# schematic.net
KiCad netlist of a schematic drawn in EAGLE
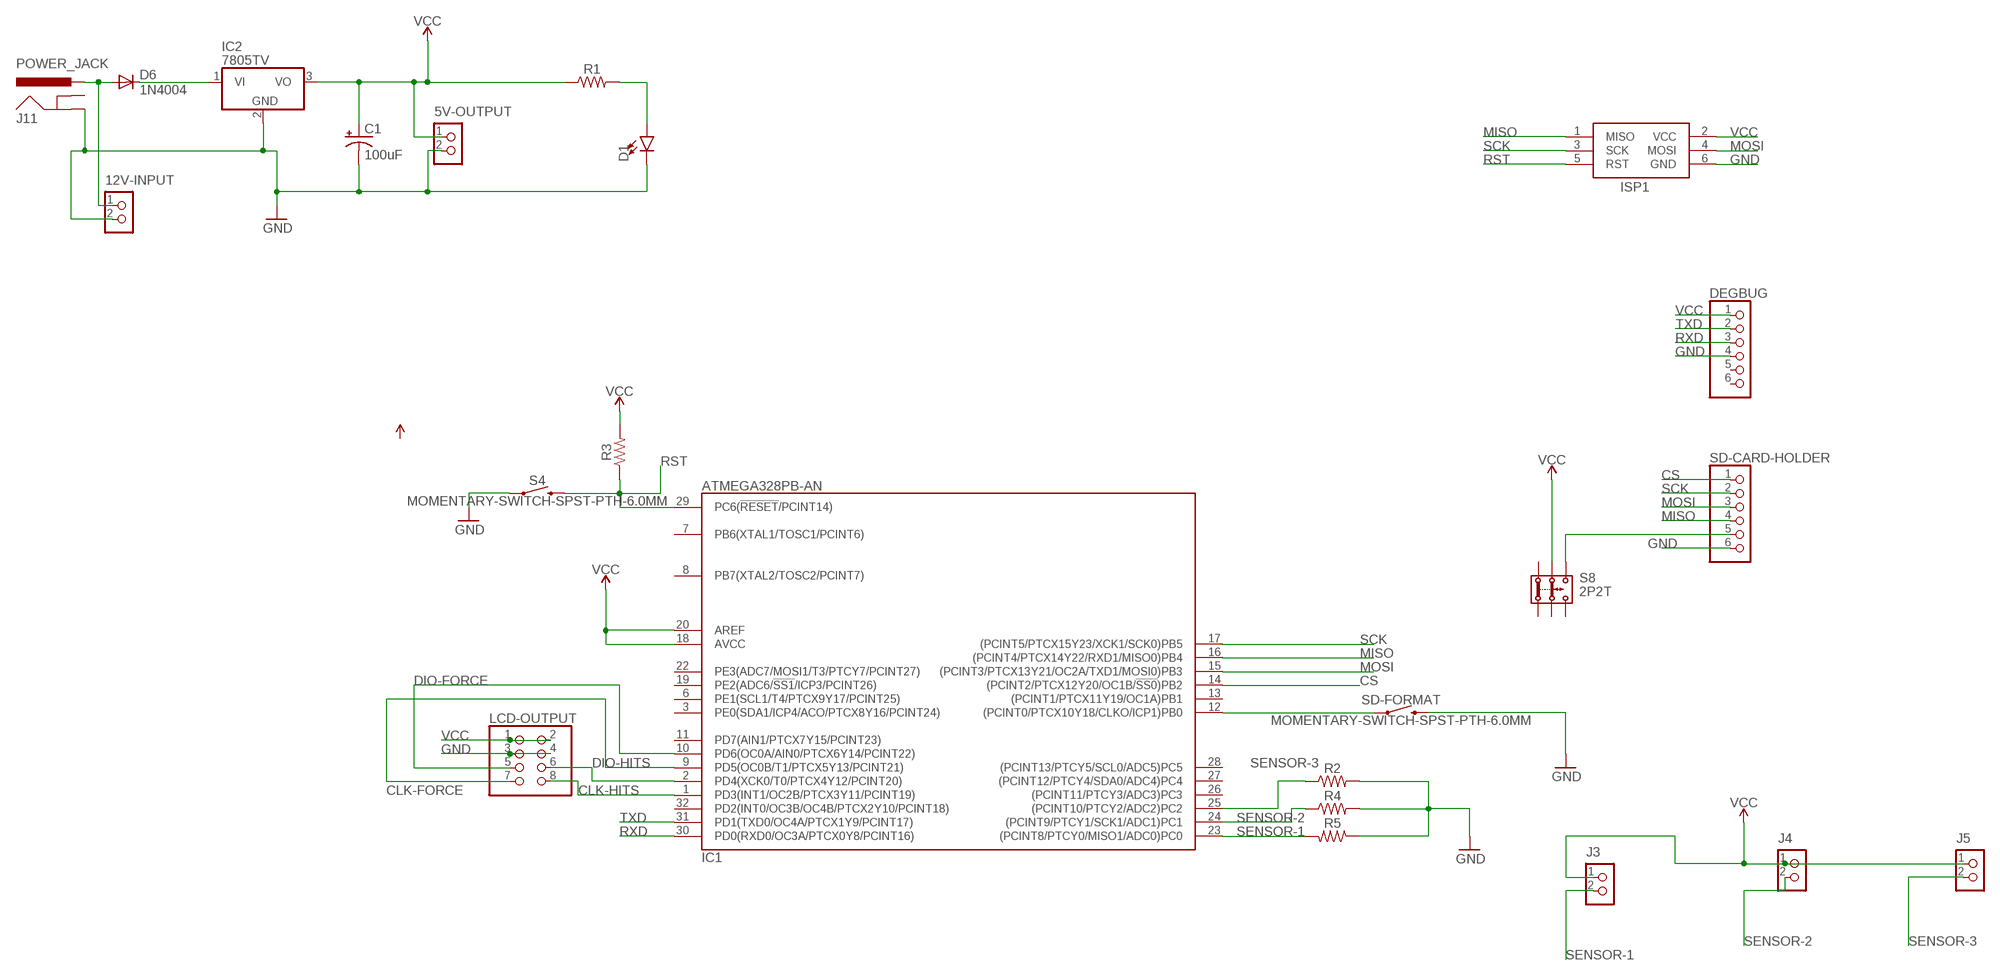
[diagram p0: schematic, sheet 1]

(export (version "E")
  (design (tool "Eeschema 10.0.6"))
  (components
    (comp (ref "5V-OUTPUT")
      (value "CON_TERMINAL_BLOCK_02-5MM")
      (footprint "eagle-import:TERMINAL_BLOCK_2P_5")
      (libsource (lib "eagle-import") (part "CON_TERMINAL_BLOCK_02-5MM"))
    )
    (comp (ref "12V-INPUT")
      (value "CON_TERMINAL_BLOCK_02-5MM")
      (footprint "eagle-import:TERMINAL_BLOCK_2P_5")
      (libsource (lib "eagle-import") (part "CON_TERMINAL_BLOCK_02-5MM"))
    )
    (comp (ref "C1")
      (value "100uF")
      (footprint "eagle-import:CPOL-RADIAL-2.5MM-6.5MM")
      (libsource (lib "eagle-import") (part "100UF-POLAR-RADIAL-2.5MM-25V-20%"))
    )
    (comp (ref "D1")
      (value "LED1206")
      (footprint "eagle-import:LED-1206")
      (libsource (lib "eagle-import") (part "LED1206"))
    )
    (comp (ref "D6")
      (value "1N4004")
      (footprint "eagle-import:DO41-10")
      (libsource (lib "eagle-import") (part "1N4004"))
    )
    (comp (ref "DEGBUG")
      (value "PINHD-1X6")
      (footprint "eagle-import:1X06")
      (libsource (lib "eagle-import") (part "PINHD-1X6"))
    )
    (comp (ref "IC1")
      (value "ATMEGA328PB-AN")
      (footprint "eagle-import:QFP32_7X7_0.80")
      (libsource (lib "eagle-import") (part "ATMEGA328PB-AN"))
    )
    (comp (ref "IC2")
      (value "7805TV")
      (footprint "eagle-import:TO220V")
      (libsource (lib "eagle-import") (part "78TV05"))
    )
    (comp (ref "ISP1")
      (value "AVRISP-6")
      (footprint "eagle-import:AVRISP")
      (libsource (lib "eagle-import") (part "AVRISP-6"))
    )
    (comp (ref "J3")
      (value "CON_TERMINAL_BLOCK_02-5MM")
      (footprint "eagle-import:TERMINAL_BLOCK_2P_5")
      (libsource (lib "eagle-import") (part "CON_TERMINAL_BLOCK_02-5MM"))
    )
    (comp (ref "J4")
      (value "CON_TERMINAL_BLOCK_02-5MM")
      (footprint "eagle-import:TERMINAL_BLOCK_2P_5")
      (libsource (lib "eagle-import") (part "CON_TERMINAL_BLOCK_02-5MM"))
    )
    (comp (ref "J5")
      (value "CON_TERMINAL_BLOCK_02-5MM")
      (footprint "eagle-import:TERMINAL_BLOCK_2P_5")
      (libsource (lib "eagle-import") (part "CON_TERMINAL_BLOCK_02-5MM"))
    )
    (comp (ref "J11")
      (value "POWER_JACK")
      (footprint "eagle-import:POWER_JACK_PTH")
      (libsource (lib "eagle-import") (part "POWER_JACK"))
    )
    (comp (ref "LCD-OUTPUT")
      (value "PINHD-2X4")
      (footprint "eagle-import:2X04")
      (libsource (lib "eagle-import") (part "PINHD-2X4"))
    )
    (comp (ref "R1")
      (value "RESISTOR1206")
      (footprint "eagle-import:1206")
      (libsource (lib "eagle-import") (part "RESISTOR1206"))
    )
    (comp (ref "R2")
      (value "RESISTOR1206")
      (footprint "eagle-import:1206")
      (libsource (lib "eagle-import") (part "RESISTOR1206"))
    )
    (comp (ref "R3")
      (value "RESISTOR1206")
      (footprint "eagle-import:1206")
      (libsource (lib "eagle-import") (part "RESISTOR1206"))
    )
    (comp (ref "R4")
      (value "RESISTOR1206")
      (footprint "eagle-import:1206")
      (libsource (lib "eagle-import") (part "RESISTOR1206"))
    )
    (comp (ref "R5")
      (value "RESISTOR1206")
      (footprint "eagle-import:1206")
      (libsource (lib "eagle-import") (part "RESISTOR1206"))
    )
    (comp (ref "S4")
      (value "MOMENTARY-SWITCH-SPST-PTH-6.0MM")
      (footprint "eagle-import:TACTILE_SWITCH_PTH_6.0MM")
      (libsource (lib "eagle-import") (part "MOMENTARY-SWITCH-SPST-PTH-6.0MM"))
    )
    (comp (ref "S8")
      (value "2P2T")
      (footprint "eagle-import:2P2T")
      (libsource (lib "eagle-import") (part "2P2T"))
    )
    (comp (ref "SD-CARD-HOLDER")
      (value "PINHD-1X6")
      (footprint "eagle-import:1X06")
      (libsource (lib "eagle-import") (part "PINHD-1X6"))
    )
    (comp (ref "SD-FORMAT")
      (value "MOMENTARY-SWITCH-SPST-PTH-6.0MM")
      (footprint "eagle-import:TACTILE_SWITCH_PTH_6.0MM")
      (libsource (lib "eagle-import") (part "MOMENTARY-SWITCH-SPST-PTH-6.0MM"))
    )
  )
  (nets
    (net (code "1") (name "/CLK-FORCE") (class "Default")
      (node (ref "IC1") (pin "9") (pinfunction "PD5(OC0B/T1/PTCX5Y13/PCINT21)_9") (pintype "bidirectional"))
      (node (ref "LCD-OUTPUT") (pin "7") (pinfunction "7_7") (pintype "passive"))
    )
    (net (code "2") (name "/CLK-HITS") (class "Default")
      (node (ref "IC1") (pin "1") (pinfunction "PD3(INT1/OC2B/PTCX3Y11/PCINT19)_1") (pintype "bidirectional"))
      (node (ref "LCD-OUTPUT") (pin "8") (pinfunction "8_8") (pintype "passive"))
    )
    (net (code "3") (name "/CS") (class "Default")
      (node (ref "IC1") (pin "14") (pinfunction "(PCINT2/PTCX12Y20/OC1B/~{SS0})PB2_14") (pintype "bidirectional"))
      (node (ref "SD-CARD-HOLDER") (pin "1") (pinfunction "1_1") (pintype "passive"))
    )
    (net (code "4") (name "/DIO-FORCE") (class "Default")
      (node (ref "IC1") (pin "10") (pinfunction "PD6(OC0A/AIN0/PTCX6Y14/PCINT22)_10") (pintype "bidirectional"))
      (node (ref "LCD-OUTPUT") (pin "5") (pinfunction "5_5") (pintype "passive"))
    )
    (net (code "5") (name "/DIO-HITS") (class "Default")
      (node (ref "IC1") (pin "2") (pinfunction "PD4(XCK0/T0/PTCX4Y12/PCINT20)_2") (pintype "bidirectional"))
      (node (ref "LCD-OUTPUT") (pin "6") (pinfunction "6_6") (pintype "passive"))
    )
    (net (code "6") (name "/MISO") (class "Default")
      (node (ref "IC1") (pin "16") (pinfunction "(PCINT4/PTCX14Y22/RXD1/MISO0)PB4_16") (pintype "bidirectional"))
      (node (ref "ISP1") (pin "1") (pinfunction "MISO_1") (pintype "input"))
      (node (ref "SD-CARD-HOLDER") (pin "4") (pinfunction "4_4") (pintype "passive"))
    )
    (net (code "7") (name "/MOSI") (class "Default")
      (node (ref "IC1") (pin "15") (pinfunction "(PCINT3/PTCX13Y21/OC2A/TXD1/MOSI0)PB3_15") (pintype "bidirectional"))
      (node (ref "ISP1") (pin "4") (pinfunction "MOSI_4") (pintype "output"))
      (node (ref "SD-CARD-HOLDER") (pin "3") (pinfunction "3_3") (pintype "passive"))
    )
    (net (code "8") (name "/RST") (class "Default")
      (node (ref "IC1") (pin "29") (pinfunction "PC6(~{RESET}/PCINT14)_29") (pintype "bidirectional"))
      (node (ref "ISP1") (pin "5") (pinfunction "RST_5") (pintype "output"))
      (node (ref "R3") (pin "1") (pinfunction "1_1") (pintype "passive"))
      (node (ref "S4") (pin "3") (pinfunction "2_3") (pintype "passive"))
    )
    (net (code "9") (name "/RXD") (class "Default")
      (node (ref "DEGBUG") (pin "3") (pinfunction "3_3") (pintype "passive"))
      (node (ref "IC1") (pin "30") (pinfunction "PD0(RXD0/OC3A/PTCX0Y8/PCINT16)_30") (pintype "bidirectional"))
    )
    (net (code "10") (name "/SCK") (class "Default")
      (node (ref "IC1") (pin "17") (pinfunction "(PCINT5/PTCX15Y23/XCK1/SCK0)PB5_17") (pintype "bidirectional"))
      (node (ref "ISP1") (pin "3") (pinfunction "SCK_3") (pintype "output"))
      (node (ref "SD-CARD-HOLDER") (pin "2") (pinfunction "2_2") (pintype "passive"))
    )
    (net (code "11") (name "/SENSOR-1") (class "Default")
      (node (ref "IC1") (pin "23") (pinfunction "(PCINT8/PTCY0/MISO1/ADC0)PC0_23") (pintype "bidirectional"))
      (node (ref "J3") (pin "2") (pinfunction "2_2") (pintype "passive"))
      (node (ref "R5") (pin "2") (pinfunction "2_2") (pintype "passive"))
    )
    (net (code "12") (name "/SENSOR-2") (class "Default")
      (node (ref "IC1") (pin "24") (pinfunction "(PCINT9/PTCY1/SCK1/ADC1)PC1_24") (pintype "bidirectional"))
      (node (ref "J4") (pin "2") (pinfunction "2_2") (pintype "passive"))
      (node (ref "R4") (pin "1") (pinfunction "1_1") (pintype "passive"))
    )
    (net (code "13") (name "/SENSOR-3") (class "Default")
      (node (ref "IC1") (pin "25") (pinfunction "(PCINT10/PTCY2/ADC2)PC2_25") (pintype "bidirectional"))
      (node (ref "J5") (pin "2") (pinfunction "2_2") (pintype "passive"))
      (node (ref "R2") (pin "1") (pinfunction "1_1") (pintype "passive"))
    )
    (net (code "14") (name "/TXD") (class "Default")
      (node (ref "DEGBUG") (pin "2") (pinfunction "2_2") (pintype "passive"))
      (node (ref "IC1") (pin "31") (pinfunction "PD1(TXD0/OC4A/PTCX1Y9/PCINT17)_31") (pintype "bidirectional"))
    )
    (net (code "15") (name "GND") (class "Default")
      (node (ref "12V-INPUT") (pin "2") (pinfunction "2_2") (pintype "passive"))
      (node (ref "5V-OUTPUT") (pin "2") (pinfunction "2_2") (pintype "passive"))
      (node (ref "C1") (pin "2") (pinfunction "-_2") (pintype "passive"))
      (node (ref "D1") (pin "C") (pinfunction "C_C") (pintype "passive"))
      (node (ref "DEGBUG") (pin "4") (pinfunction "4_4") (pintype "passive"))
      (node (ref "IC2") (pin "2") (pinfunction "GND_2") (pintype "passive"))
      (node (ref "ISP1") (pin "6") (pinfunction "GND_6") (pintype "power_in"))
      (node (ref "J11") (pin "GND") (pinfunction "GND_GND") (pintype "bidirectional"))
      (node (ref "LCD-OUTPUT") (pin "3") (pinfunction "3_3") (pintype "passive"))
      (node (ref "LCD-OUTPUT") (pin "4") (pinfunction "4_4") (pintype "passive"))
      (node (ref "R2") (pin "2") (pinfunction "2_2") (pintype "passive"))
      (node (ref "R4") (pin "2") (pinfunction "2_2") (pintype "passive"))
      (node (ref "R5") (pin "1") (pinfunction "1_1") (pintype "passive"))
      (node (ref "S4") (pin "1") (pinfunction "1_1") (pintype "passive"))
      (node (ref "SD-CARD-HOLDER") (pin "6") (pinfunction "6_6") (pintype "passive"))
      (node (ref "SD-FORMAT") (pin "3") (pinfunction "2_3") (pintype "passive"))
    )
    (net (code "16") (name "Net-(12V-INPUT-Pad1)") (class "Default")
      (node (ref "12V-INPUT") (pin "1") (pinfunction "1_1") (pintype "passive"))
      (node (ref "D6") (pin "A") (pinfunction "A_A") (pintype "passive"))
      (node (ref "J11") (pin "PWR") (pinfunction "PWR_PWR") (pintype "bidirectional"))
    )
    (net (code "17") (name "Net-(D1-PadA)") (class "Default")
      (node (ref "D1") (pin "A") (pinfunction "A_A") (pintype "passive"))
      (node (ref "R1") (pin "2") (pinfunction "2_2") (pintype "passive"))
    )
    (net (code "18") (name "Net-(IC1A-(PCINT0{slash}PTCX10Y18{slash}CLKO{slash}ICP1)PB0)") (class "Default")
      (node (ref "IC1") (pin "12") (pinfunction "(PCINT0/PTCX10Y18/CLKO/ICP1)PB0_12") (pintype "bidirectional"))
      (node (ref "SD-FORMAT") (pin "1") (pinfunction "1_1") (pintype "passive"))
    )
    (net (code "19") (name "Net-(IC2-VI)") (class "Default")
      (node (ref "D6") (pin "C") (pinfunction "C_C") (pintype "passive"))
      (node (ref "IC2") (pin "1") (pinfunction "VI_1") (pintype "input"))
    )
    (net (code "20") (name "Net-(S8-Pad3.1)") (class "Default")
      (node (ref "S8") (pin "3.1") (pinfunction "3.1_3.1") (pintype "passive"))
      (node (ref "SD-CARD-HOLDER") (pin "5") (pinfunction "5_5") (pintype "passive"))
    )
    (net (code "21") (name "VCC") (class "Default")
      (node (ref "5V-OUTPUT") (pin "1") (pinfunction "1_1") (pintype "passive"))
      (node (ref "C1") (pin "1") (pinfunction "+_1") (pintype "passive"))
      (node (ref "DEGBUG") (pin "1") (pinfunction "1_1") (pintype "passive"))
      (node (ref "IC1") (pin "18") (pinfunction "AVCC_18") (pintype "power_in"))
      (node (ref "IC1") (pin "20") (pinfunction "AREF_20") (pintype "passive"))
      (node (ref "IC2") (pin "3") (pinfunction "VO_3") (pintype "passive"))
      (node (ref "ISP1") (pin "2") (pinfunction "VCC_2") (pintype "power_in"))
      (node (ref "J3") (pin "1") (pinfunction "1_1") (pintype "passive"))
      (node (ref "J4") (pin "1") (pinfunction "1_1") (pintype "passive"))
      (node (ref "J5") (pin "1") (pinfunction "1_1") (pintype "passive"))
      (node (ref "LCD-OUTPUT") (pin "1") (pinfunction "1_1") (pintype "passive"))
      (node (ref "LCD-OUTPUT") (pin "2") (pinfunction "2_2") (pintype "passive"))
      (node (ref "R1") (pin "1") (pinfunction "1_1") (pintype "passive"))
      (node (ref "R3") (pin "2") (pinfunction "2_2") (pintype "passive"))
      (node (ref "S8") (pin "2.1") (pinfunction "2.1_2.1") (pintype "passive"))
    )
    (net (code "22") (name "unconnected-(DEGBUG-Pad5)") (class "Default")
      (node (ref "DEGBUG") (pin "5") (pinfunction "5_5") (pintype "passive"))
    )
    (net (code "23") (name "unconnected-(DEGBUG-Pad6)") (class "Default")
      (node (ref "DEGBUG") (pin "6") (pinfunction "6_6") (pintype "passive"))
    )
    (net (code "24") (name "unconnected-(IC1A-(PCINT1{slash}PTCX11Y19{slash}OC1A)PB1-Pad13)") (class "Default")
      (node (ref "IC1") (pin "13") (pinfunction "(PCINT1/PTCX11Y19/OC1A)PB1_13") (pintype "bidirectional"))
    )
    (net (code "25") (name "unconnected-(IC1A-(PCINT11{slash}PTCY3{slash}ADC3)PC3-Pad26)") (class "Default")
      (node (ref "IC1") (pin "26") (pinfunction "(PCINT11/PTCY3/ADC3)PC3_26") (pintype "bidirectional"))
    )
    (net (code "26") (name "unconnected-(IC1A-(PCINT12{slash}PTCY4{slash}SDA0{slash}ADC4)PC4-Pad27)") (class "Default")
      (node (ref "IC1") (pin "27") (pinfunction "(PCINT12/PTCY4/SDA0/ADC4)PC4_27") (pintype "bidirectional"))
    )
    (net (code "27") (name "unconnected-(IC1A-(PCINT13{slash}PTCY5{slash}SCL0{slash}ADC5)PC5-Pad28)") (class "Default")
      (node (ref "IC1") (pin "28") (pinfunction "(PCINT13/PTCY5/SCL0/ADC5)PC5_28") (pintype "bidirectional"))
    )
    (net (code "28") (name "unconnected-(IC1A-PB6(XTAL1{slash}TOSC1{slash}PCINT6)-Pad7)") (class "Default")
      (node (ref "IC1") (pin "7") (pinfunction "PB6(XTAL1/TOSC1/PCINT6)_7") (pintype "bidirectional"))
    )
    (net (code "29") (name "unconnected-(IC1A-PB7(XTAL2{slash}TOSC2{slash}PCINT7)-Pad8)") (class "Default")
      (node (ref "IC1") (pin "8") (pinfunction "PB7(XTAL2/TOSC2/PCINT7)_8") (pintype "bidirectional"))
    )
    (net (code "30") (name "unconnected-(IC1A-PD2(INT0{slash}OC3B{slash}OC4B{slash}PTCX2Y10{slash}PCINT18)-Pad32)") (class "Default")
      (node (ref "IC1") (pin "32") (pinfunction "PD2(INT0/OC3B/OC4B/PTCX2Y10/PCINT18)_32") (pintype "bidirectional"))
    )
    (net (code "31") (name "unconnected-(IC1A-PD7(AIN1{slash}PTCX7Y15{slash}PCINT23)-Pad11)") (class "Default")
      (node (ref "IC1") (pin "11") (pinfunction "PD7(AIN1/PTCX7Y15/PCINT23)_11") (pintype "bidirectional"))
    )
    (net (code "32") (name "unconnected-(IC1A-PE0(SDA1{slash}ICP4{slash}ACO{slash}PTCX8Y16{slash}PCINT24)-Pad3)") (class "Default")
      (node (ref "IC1") (pin "3") (pinfunction "PE0(SDA1/ICP4/ACO/PTCX8Y16/PCINT24)_3") (pintype "bidirectional"))
    )
    (net (code "33") (name "unconnected-(IC1A-PE1(SCL1{slash}T4{slash}PTCX9Y17{slash}PCINT25)-Pad6)") (class "Default")
      (node (ref "IC1") (pin "6") (pinfunction "PE1(SCL1/T4/PTCX9Y17/PCINT25)_6") (pintype "bidirectional"))
    )
    (net (code "34") (name "unconnected-(IC1A-PE2(ADC6{slash}~{SS1}{slash}ICP3{slash}PCINT26)-Pad19)") (class "Default")
      (node (ref "IC1") (pin "19") (pinfunction "PE2(ADC6/~{SS1}/ICP3/PCINT26)_19") (pintype "bidirectional"))
    )
    (net (code "35") (name "unconnected-(IC1A-PE3(ADC7{slash}MOSI1{slash}T3{slash}PTCY7{slash}PCINT27)-Pad22)") (class "Default")
      (node (ref "IC1") (pin "22") (pinfunction "PE3(ADC7/MOSI1/T3/PTCY7/PCINT27)_22") (pintype "bidirectional"))
    )
    (net (code "36") (name "unconnected-(J11-PadGNDBREAK)") (class "Default")
      (node (ref "J11") (pin "GNDBREAK") (pinfunction "GNDBREAK_GNDBREAK") (pintype "bidirectional"))
    )
    (net (code "37") (name "unconnected-(S8-Pad1.1)") (class "Default")
      (node (ref "S8") (pin "1.1") (pinfunction "1.1_1.1") (pintype "passive"))
    )
    (net (code "38") (name "unconnected-(S8-Pad1.2)") (class "Default")
      (node (ref "S8") (pin "1.2") (pinfunction "1.2_1.2") (pintype "passive"))
    )
    (net (code "39") (name "unconnected-(S8-Pad2.2)") (class "Default")
      (node (ref "S8") (pin "2.2") (pinfunction "2.2_2.2") (pintype "passive"))
    )
    (net (code "40") (name "unconnected-(S8-Pad3.2)") (class "Default")
      (node (ref "S8") (pin "3.2") (pinfunction "3.2_3.2") (pintype "passive"))
    )
  )
)
